# Schematic1.net
KiCad netlist of a schematic drawn in EAGLE
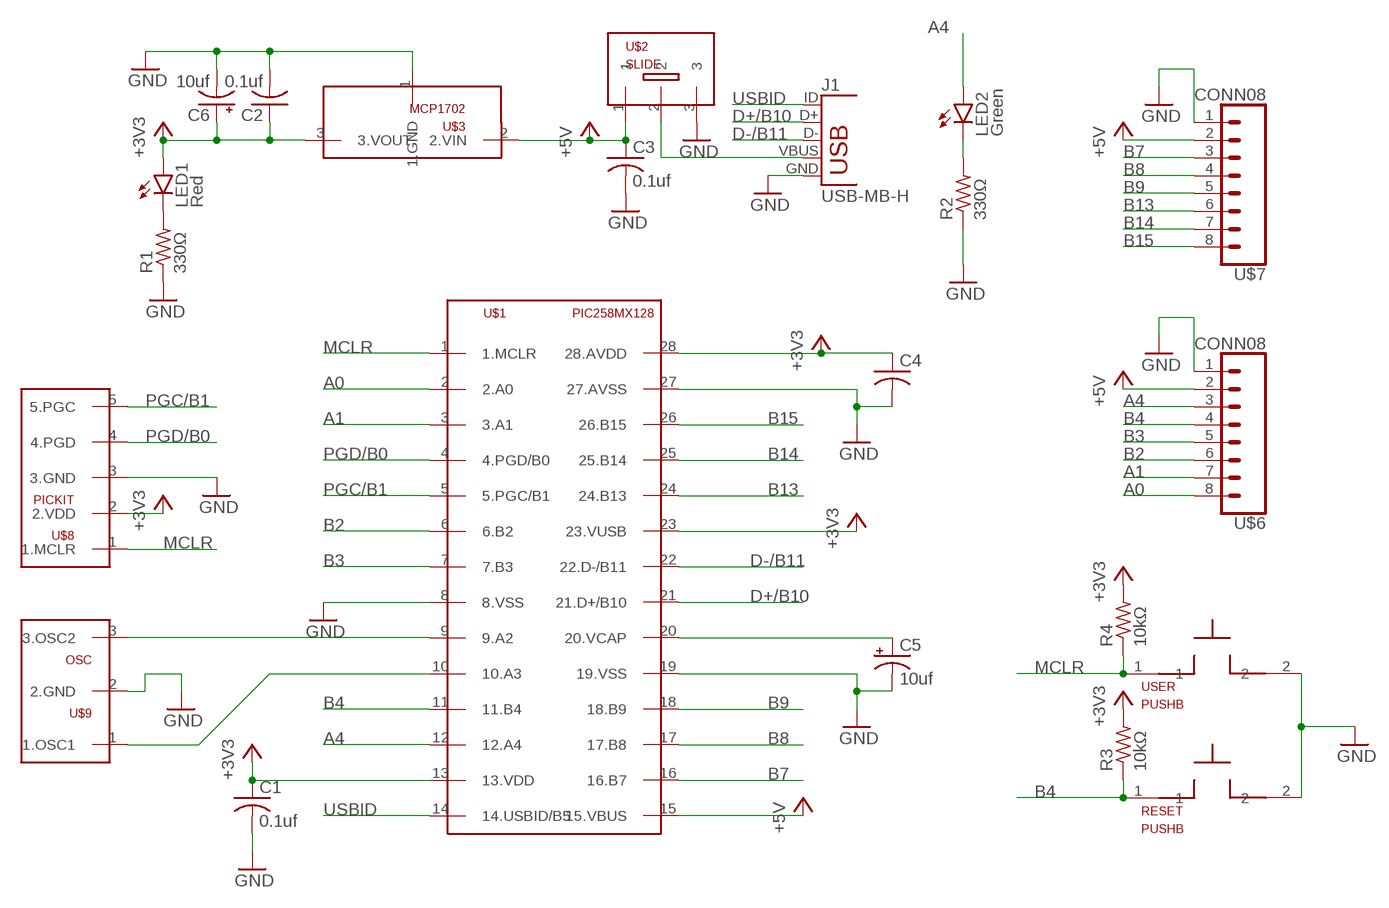
[diagram p0: schematic, sheet 1]

(export (version "E")
  (design (tool "Eeschema 10.0.6"))
  (components
    (comp (ref "C1")
      (value "0.1uf")
      (footprint "eagle-import:C025-025X050")
      (libsource (lib "eagle-import") (part "C-US025-025X050"))
    )
    (comp (ref "C2")
      (value "0.1uf")
      (footprint "eagle-import:C025-025X050")
      (libsource (lib "eagle-import") (part "C-US025-025X050"))
    )
    (comp (ref "C3")
      (value "0.1uf")
      (footprint "eagle-import:C025-025X050")
      (libsource (lib "eagle-import") (part "C-US025-025X050"))
    )
    (comp (ref "C4")
      (value "C-US025-025X050")
      (footprint "eagle-import:C025-025X050")
      (libsource (lib "eagle-import") (part "C-US025-025X050"))
    )
    (comp (ref "C5")
      (value "10uf")
      (footprint "eagle-import:B45181B")
      (libsource (lib "eagle-import") (part "CPOL-USB45181B"))
    )
    (comp (ref "C6")
      (value "10uf")
      (footprint "eagle-import:B45181B")
      (libsource (lib "eagle-import") (part "CPOL-USB45181B"))
    )
    (comp (ref "J1")
      (value "USB-MB-H")
      (footprint "eagle-import:USB-MB-H")
      (libsource (lib "eagle-import") (part "USB-MB-H"))
    )
    (comp (ref "LED1")
      (value "Red")
      (footprint "eagle-import:LED3MM")
      (libsource (lib "eagle-import") (part "LED3MM"))
    )
    (comp (ref "LED2")
      (value "Green")
      (footprint "eagle-import:LED3MM")
      (libsource (lib "eagle-import") (part "LED3MM"))
    )
    (comp (ref "R1")
      (value "330Ω")
      (footprint "eagle-import:0207_10")
      (libsource (lib "eagle-import") (part "R-US_0207/10"))
    )
    (comp (ref "R2")
      (value "330Ω")
      (footprint "eagle-import:0207_10")
      (libsource (lib "eagle-import") (part "R-US_0207/10"))
    )
    (comp (ref "R3")
      (value "10kΩ")
      (footprint "eagle-import:0207_10")
      (libsource (lib "eagle-import") (part "R-US_0207/10"))
    )
    (comp (ref "R4")
      (value "10kΩ")
      (footprint "eagle-import:0207_10")
      (libsource (lib "eagle-import") (part "R-US_0207/10"))
    )
    (comp (ref "RESET")
      (value "PUSHB")
      (footprint "eagle-import:PUSHB")
      (libsource (lib "eagle-import") (part "PUSHB"))
    )
    (comp (ref "U$1")
      (value "PIC258MX128")
      (footprint "eagle-import:DIL28-3")
      (libsource (lib "eagle-import") (part "PIC258MX128"))
    )
    (comp (ref "U$2")
      (value "SLIDE")
      (footprint "eagle-import:SLIDE")
      (libsource (lib "eagle-import") (part "SLIDE"))
    )
    (comp (ref "U$3")
      (value "MCP1702")
      (footprint "eagle-import:TO92")
      (libsource (lib "eagle-import") (part "MCP1702"))
    )
    (comp (ref "U$6")
      (value "CONN08")
      (footprint "eagle-import:1X08")
      (libsource (lib "eagle-import") (part "CONN08"))
    )
    (comp (ref "U$7")
      (value "CONN08")
      (footprint "eagle-import:1X08")
      (libsource (lib "eagle-import") (part "CONN08"))
    )
    (comp (ref "U$8")
      (value "PICKIT")
      (footprint "eagle-import:1X05")
      (libsource (lib "eagle-import") (part "PICKIT"))
    )
    (comp (ref "U$9")
      (value "OSC")
      (footprint "eagle-import:OSC")
      (libsource (lib "eagle-import") (part "OSC"))
    )
    (comp (ref "USER")
      (value "PUSHB")
      (footprint "eagle-import:PUSHB")
      (libsource (lib "eagle-import") (part "PUSHB"))
    )
  )
  (nets
    (net (code "1") (name "+3V3") (class "Default")
      (node (ref "C1") (pin "1") (pinfunction "1_1") (pintype "passive"))
      (node (ref "C2") (pin "1") (pinfunction "1_1") (pintype "passive"))
      (node (ref "C4") (pin "1") (pinfunction "1_1") (pintype "passive"))
      (node (ref "C6") (pin "+") (pinfunction "+_+") (pintype "passive"))
      (node (ref "LED1") (pin "A") (pinfunction "A_A") (pintype "passive"))
      (node (ref "R3") (pin "2") (pinfunction "2_2") (pintype "passive"))
      (node (ref "R4") (pin "2") (pinfunction "2_2") (pintype "passive"))
      (node (ref "U$1") (pin "13") (pinfunction "13.VDD_13") (pintype "bidirectional"))
      (node (ref "U$1") (pin "23") (pinfunction "23.VUSB_23") (pintype "bidirectional"))
      (node (ref "U$1") (pin "28") (pinfunction "28.AVDD_28") (pintype "bidirectional"))
      (node (ref "U$3") (pin "3") (pinfunction "3.VOUT_3") (pintype "bidirectional"))
      (node (ref "U$8") (pin "2") (pinfunction "2.VDD_2") (pintype "bidirectional"))
    )
    (net (code "2") (name "+5V") (class "Default")
      (node (ref "C3") (pin "1") (pinfunction "1_1") (pintype "passive"))
      (node (ref "U$1") (pin "15") (pinfunction "15.VBUS_15") (pintype "bidirectional"))
      (node (ref "U$2") (pin "1") (pinfunction "1_1") (pintype "bidirectional"))
      (node (ref "U$3") (pin "2") (pinfunction "2.VIN_2") (pintype "bidirectional"))
      (node (ref "U$6") (pin "2") (pinfunction "2_2") (pintype "passive"))
      (node (ref "U$7") (pin "2") (pinfunction "2_2") (pintype "passive"))
    )
    (net (code "3") (name "/A0") (class "Default")
      (node (ref "U$1") (pin "2") (pinfunction "2.A0_2") (pintype "bidirectional"))
      (node (ref "U$6") (pin "8") (pinfunction "8_8") (pintype "passive"))
    )
    (net (code "4") (name "/A1") (class "Default")
      (node (ref "U$1") (pin "3") (pinfunction "3.A1_3") (pintype "bidirectional"))
      (node (ref "U$6") (pin "7") (pinfunction "7_7") (pintype "passive"))
    )
    (net (code "5") (name "/A4") (class "Default")
      (node (ref "LED2") (pin "A") (pinfunction "A_A") (pintype "passive"))
      (node (ref "U$1") (pin "12") (pinfunction "12.A4_12") (pintype "bidirectional"))
      (node (ref "U$6") (pin "3") (pinfunction "3_3") (pintype "passive"))
    )
    (net (code "6") (name "/B2") (class "Default")
      (node (ref "U$1") (pin "6") (pinfunction "6.B2_6") (pintype "bidirectional"))
      (node (ref "U$6") (pin "6") (pinfunction "6_6") (pintype "passive"))
    )
    (net (code "7") (name "/B3") (class "Default")
      (node (ref "U$1") (pin "7") (pinfunction "7.B3_7") (pintype "bidirectional"))
      (node (ref "U$6") (pin "5") (pinfunction "5_5") (pintype "passive"))
    )
    (net (code "8") (name "/B4") (class "Default")
      (node (ref "R3") (pin "1") (pinfunction "1_1") (pintype "passive"))
      (node (ref "RESET") (pin "1") (pinfunction "1_1") (pintype "bidirectional"))
      (node (ref "U$1") (pin "11") (pinfunction "11.B4_11") (pintype "bidirectional"))
      (node (ref "U$6") (pin "4") (pinfunction "4_4") (pintype "passive"))
    )
    (net (code "9") (name "/B7") (class "Default")
      (node (ref "U$1") (pin "16") (pinfunction "16.B7_16") (pintype "bidirectional"))
      (node (ref "U$7") (pin "3") (pinfunction "3_3") (pintype "passive"))
    )
    (net (code "10") (name "/B8") (class "Default")
      (node (ref "U$1") (pin "17") (pinfunction "17.B8_17") (pintype "bidirectional"))
      (node (ref "U$7") (pin "4") (pinfunction "4_4") (pintype "passive"))
    )
    (net (code "11") (name "/B9") (class "Default")
      (node (ref "U$1") (pin "18") (pinfunction "18.B9_18") (pintype "bidirectional"))
      (node (ref "U$7") (pin "5") (pinfunction "5_5") (pintype "passive"))
    )
    (net (code "12") (name "/B13") (class "Default")
      (node (ref "U$1") (pin "24") (pinfunction "24.B13_24") (pintype "bidirectional"))
      (node (ref "U$7") (pin "6") (pinfunction "6_6") (pintype "passive"))
    )
    (net (code "13") (name "/B14") (class "Default")
      (node (ref "U$1") (pin "25") (pinfunction "25.B14_25") (pintype "bidirectional"))
      (node (ref "U$7") (pin "7") (pinfunction "7_7") (pintype "passive"))
    )
    (net (code "14") (name "/B15") (class "Default")
      (node (ref "U$1") (pin "26") (pinfunction "26.B15_26") (pintype "bidirectional"))
      (node (ref "U$7") (pin "8") (pinfunction "8_8") (pintype "passive"))
    )
    (net (code "15") (name "/D+{slash}B10") (class "Default")
      (node (ref "J1") (pin "D+") (pinfunction "D+_D+") (pintype "bidirectional"))
      (node (ref "U$1") (pin "21") (pinfunction "21.D+/B10_21") (pintype "bidirectional"))
    )
    (net (code "16") (name "/D-{slash}B11") (class "Default")
      (node (ref "J1") (pin "D-") (pinfunction "D-_D-") (pintype "bidirectional"))
      (node (ref "U$1") (pin "22") (pinfunction "22.D-/B11_22") (pintype "bidirectional"))
    )
    (net (code "17") (name "/MCLR") (class "Default")
      (node (ref "R4") (pin "1") (pinfunction "1_1") (pintype "passive"))
      (node (ref "U$1") (pin "1") (pinfunction "1.MCLR_1") (pintype "bidirectional"))
      (node (ref "U$8") (pin "1") (pinfunction "1.MCLR_1") (pintype "bidirectional"))
      (node (ref "USER") (pin "1") (pinfunction "1_1") (pintype "bidirectional"))
    )
    (net (code "18") (name "/PGC{slash}B1") (class "Default")
      (node (ref "U$1") (pin "5") (pinfunction "5.PGC/B1_5") (pintype "bidirectional"))
      (node (ref "U$8") (pin "5") (pinfunction "5.PGC_5") (pintype "bidirectional"))
    )
    (net (code "19") (name "/PGD{slash}B0") (class "Default")
      (node (ref "U$1") (pin "4") (pinfunction "4.PGD/B0_4") (pintype "bidirectional"))
      (node (ref "U$8") (pin "4") (pinfunction "4.PGD_4") (pintype "bidirectional"))
    )
    (net (code "20") (name "/USBID") (class "Default")
      (node (ref "J1") (pin "ID") (pinfunction "ID_ID") (pintype "bidirectional"))
      (node (ref "U$1") (pin "14") (pinfunction "14.USBID/B5_14") (pintype "bidirectional"))
    )
    (net (code "21") (name "GND") (class "Default")
      (node (ref "C1") (pin "2") (pinfunction "2_2") (pintype "passive"))
      (node (ref "C2") (pin "2") (pinfunction "2_2") (pintype "passive"))
      (node (ref "C3") (pin "2") (pinfunction "2_2") (pintype "passive"))
      (node (ref "C4") (pin "2") (pinfunction "2_2") (pintype "passive"))
      (node (ref "C5") (pin "-") (pinfunction "-_-") (pintype "passive"))
      (node (ref "C6") (pin "-") (pinfunction "-_-") (pintype "passive"))
      (node (ref "J1") (pin "GND") (pinfunction "GND_GND") (pintype "bidirectional"))
      (node (ref "R1") (pin "1") (pinfunction "1_1") (pintype "passive"))
      (node (ref "R2") (pin "1") (pinfunction "1_1") (pintype "passive"))
      (node (ref "RESET") (pin "2") (pinfunction "2_2") (pintype "bidirectional"))
      (node (ref "U$1") (pin "19") (pinfunction "19.VSS_19") (pintype "bidirectional"))
      (node (ref "U$1") (pin "27") (pinfunction "27.AVSS_27") (pintype "bidirectional"))
      (node (ref "U$1") (pin "8") (pinfunction "8.VSS_8") (pintype "bidirectional"))
      (node (ref "U$2") (pin "3") (pinfunction "3_3") (pintype "bidirectional"))
      (node (ref "U$3") (pin "1") (pinfunction "1.GND_1") (pintype "bidirectional"))
      (node (ref "U$6") (pin "1") (pinfunction "1_1") (pintype "passive"))
      (node (ref "U$7") (pin "1") (pinfunction "1_1") (pintype "passive"))
      (node (ref "U$8") (pin "3") (pinfunction "3.GND_3") (pintype "bidirectional"))
      (node (ref "U$9") (pin "2") (pinfunction "2.GND_2") (pintype "bidirectional"))
      (node (ref "USER") (pin "2") (pinfunction "2_2") (pintype "bidirectional"))
    )
    (net (code "22") (name "Net-(J1-PadVBUS)") (class "Default")
      (node (ref "J1") (pin "VBUS") (pinfunction "VBUS_VBUS") (pintype "bidirectional"))
      (node (ref "U$2") (pin "2") (pinfunction "2_2") (pintype "bidirectional"))
    )
    (net (code "23") (name "Net-(LED1-C)") (class "Default")
      (node (ref "LED1") (pin "K") (pinfunction "C_K") (pintype "passive"))
      (node (ref "R1") (pin "2") (pinfunction "2_2") (pintype "passive"))
    )
    (net (code "24") (name "Net-(LED2-C)") (class "Default")
      (node (ref "LED2") (pin "K") (pinfunction "C_K") (pintype "passive"))
      (node (ref "R2") (pin "2") (pinfunction "2_2") (pintype "passive"))
    )
    (net (code "25") (name "Net-(U$1-9.A2)") (class "Default")
      (node (ref "U$1") (pin "9") (pinfunction "9.A2_9") (pintype "bidirectional"))
      (node (ref "U$9") (pin "3") (pinfunction "3.OSC2_3") (pintype "bidirectional"))
    )
    (net (code "26") (name "Net-(U$1-10.A3)") (class "Default")
      (node (ref "U$1") (pin "10") (pinfunction "10.A3_10") (pintype "bidirectional"))
      (node (ref "U$9") (pin "1") (pinfunction "1.OSC1_1") (pintype "bidirectional"))
    )
    (net (code "27") (name "Net-(U$1-20.VCAP)") (class "Default")
      (node (ref "C5") (pin "+") (pinfunction "+_+") (pintype "passive"))
      (node (ref "U$1") (pin "20") (pinfunction "20.VCAP_20") (pintype "bidirectional"))
    )
  )
)
